# QED_2550_dos_caras.net
KiCad netlist of a schematic drawn in EAGLE
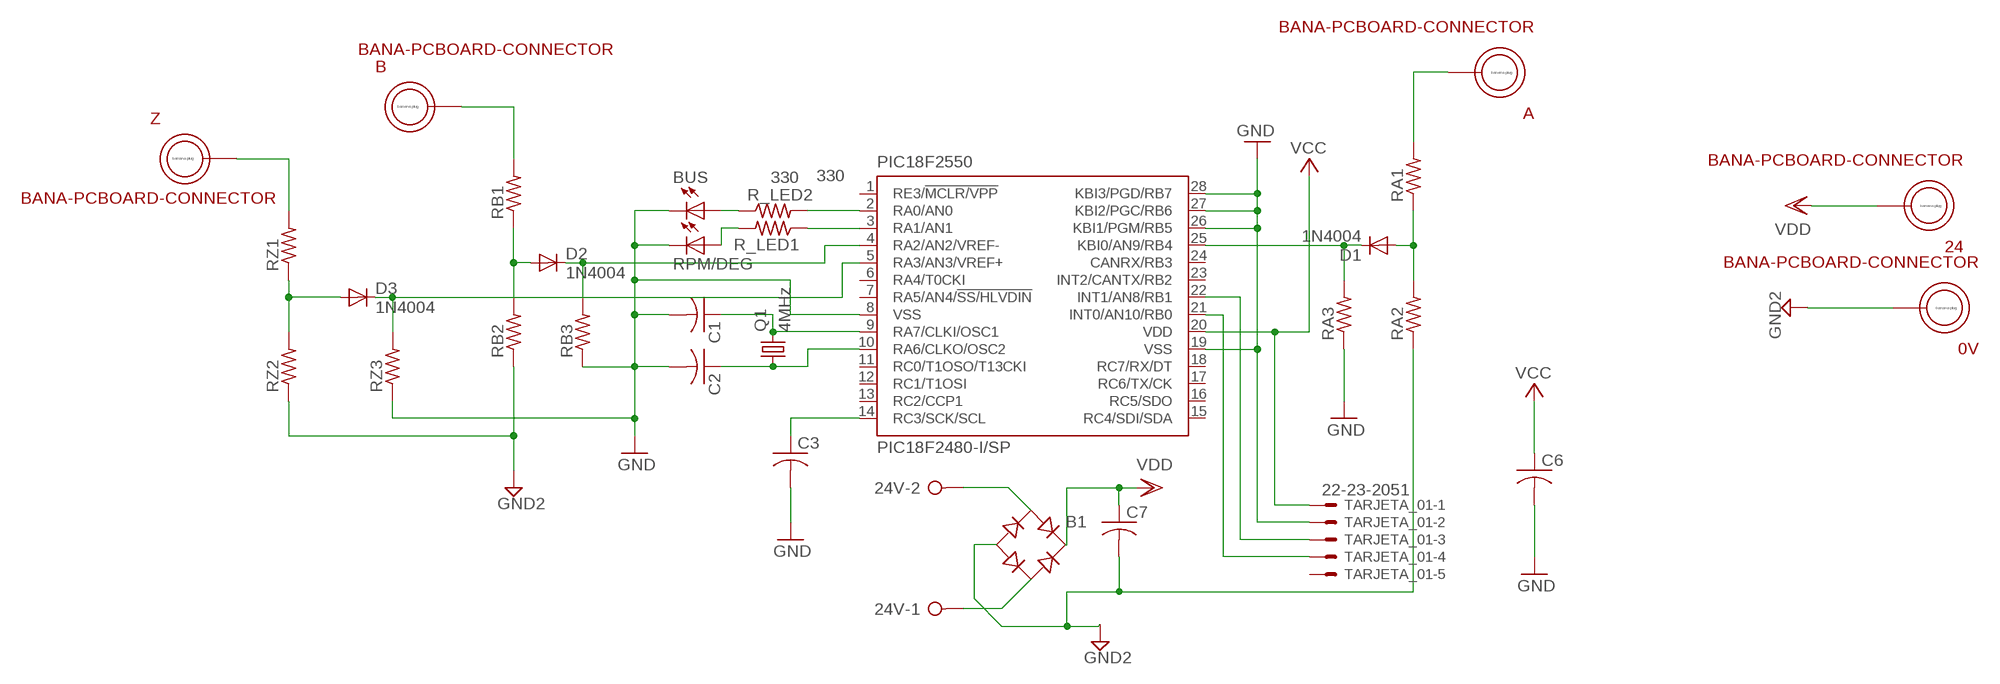
[diagram p0: schematic, sheet 1]

(export (version "E")
  (design (tool "Eeschema 10.0.6"))
  (components
    (comp (ref "0V")
      (value "BANA-PCBOARD-CONNECTOR")
      (footprint "eagle-import:BANA_PLUG")
      (libsource (lib "eagle-import") (part "BANA-PCBOARD-CONNECTOR"))
    )
    (comp (ref "24")
      (value "BANA-PCBOARD-CONNECTOR")
      (footprint "eagle-import:BANA_PLUG")
      (libsource (lib "eagle-import") (part "BANA-PCBOARD-CONNECTOR"))
    )
    (comp (ref "24V")
      (value "W237-02P")
      (footprint "eagle-import:W237-132")
      (libsource (lib "eagle-import") (part "W237-02P"))
    )
    (comp (ref "A")
      (value "BANA-PCBOARD-CONNECTOR")
      (footprint "eagle-import:BANA_PLUG")
      (libsource (lib "eagle-import") (part "BANA-PCBOARD-CONNECTOR"))
    )
    (comp (ref "B")
      (value "BANA-PCBOARD-CONNECTOR")
      (footprint "eagle-import:BANA_PLUG")
      (libsource (lib "eagle-import") (part "BANA-PCBOARD-CONNECTOR"))
    )
    (comp (ref "B1")
      (value "RB1A")
      (footprint "eagle-import:RB1A")
      (libsource (lib "eagle-import") (part "RB1A"))
    )
    (comp (ref "BUS")
      (value "LED5MM")
      (footprint "eagle-import:LED5MM")
      (libsource (lib "eagle-import") (part "LED5MM"))
    )
    (comp (ref "C1")
      (value "C-US025-024X044")
      (footprint "eagle-import:C025-024X044")
      (libsource (lib "eagle-import") (part "C-US025-024X044"))
    )
    (comp (ref "C2")
      (value "C-US025-024X044")
      (footprint "eagle-import:C025-024X044")
      (libsource (lib "eagle-import") (part "C-US025-024X044"))
    )
    (comp (ref "C3")
      (value "C-US025-024X044")
      (footprint "eagle-import:C025-024X044")
      (libsource (lib "eagle-import") (part "C-US025-024X044"))
    )
    (comp (ref "C6")
      (value "C-US025-030X050")
      (footprint "eagle-import:C025-030X050")
      (libsource (lib "eagle-import") (part "C-US025-030X050"))
    )
    (comp (ref "C7")
      (value "C-US025-030X050")
      (footprint "eagle-import:C025-030X050")
      (libsource (lib "eagle-import") (part "C-US025-030X050"))
    )
    (comp (ref "D1")
      (value "1N4004")
      (footprint "eagle-import:DO41-10")
      (libsource (lib "eagle-import") (part "1N4004"))
    )
    (comp (ref "D2")
      (value "1N4004")
      (footprint "eagle-import:DO41-10")
      (libsource (lib "eagle-import") (part "1N4004"))
    )
    (comp (ref "D3")
      (value "1N4004")
      (footprint "eagle-import:DO41-10")
      (libsource (lib "eagle-import") (part "1N4004"))
    )
    (comp (ref "PIC18F2550")
      (value "PIC18F2480-I/SP")
      (footprint "eagle-import:DIL28-3")
      (fields (field (name "MF") "MICROCHIP"))
      (libsource (lib "eagle-import") (part "PIC18F280-I/SP4"))
    )
    (comp (ref "Q1")
      (value "4MHz")
      (footprint "eagle-import:HC49_S")
      (libsource (lib "eagle-import") (part "CRYSTALHC49S"))
    )
    (comp (ref "RA1")
      (value "R-US_0204/7")
      (footprint "eagle-import:0204_7")
      (libsource (lib "eagle-import") (part "R-US_0204/7"))
    )
    (comp (ref "RA2")
      (value "R-US_0204/7")
      (footprint "eagle-import:0204_7")
      (libsource (lib "eagle-import") (part "R-US_0204/7"))
    )
    (comp (ref "RA3")
      (value "R-US_0204/7")
      (footprint "eagle-import:0204_7")
      (libsource (lib "eagle-import") (part "R-US_0204/7"))
    )
    (comp (ref "RB1")
      (value "R-US_0204/7")
      (footprint "eagle-import:0204_7")
      (libsource (lib "eagle-import") (part "R-US_0204/7"))
    )
    (comp (ref "RB2")
      (value "R-US_0204/7")
      (footprint "eagle-import:0204_7")
      (libsource (lib "eagle-import") (part "R-US_0204/7"))
    )
    (comp (ref "RB3")
      (value "R-US_0204/7")
      (footprint "eagle-import:0204_7")
      (libsource (lib "eagle-import") (part "R-US_0204/7"))
    )
    (comp (ref "RPM/DEG")
      (value "LED5MM")
      (footprint "eagle-import:LED5MM")
      (libsource (lib "eagle-import") (part "LED5MM"))
    )
    (comp (ref "RZ1")
      (value "R-US_0204/7")
      (footprint "eagle-import:0204_7")
      (libsource (lib "eagle-import") (part "R-US_0204/7"))
    )
    (comp (ref "RZ2")
      (value "R-US_0204/7")
      (footprint "eagle-import:0204_7")
      (libsource (lib "eagle-import") (part "R-US_0204/7"))
    )
    (comp (ref "RZ3")
      (value "R-US_0204/7")
      (footprint "eagle-import:0204_7")
      (libsource (lib "eagle-import") (part "R-US_0204/7"))
    )
    (comp (ref "R_LED1")
      (value "330")
      (footprint "eagle-import:0204_7")
      (libsource (lib "eagle-import") (part "R-US_0204/7"))
    )
    (comp (ref "R_LED2")
      (value "330")
      (footprint "eagle-import:0204_7")
      (libsource (lib "eagle-import") (part "R-US_0204/7"))
    )
    (comp (ref "TARJETA_01")
      (value "22-23-2051")
      (footprint "eagle-import:22-23-2051")
      (fields (field (name "MF") "MOLEX"))
      (libsource (lib "eagle-import") (part "22-23-2051"))
    )
    (comp (ref "Z")
      (value "BANA-PCBOARD-CONNECTOR")
      (footprint "eagle-import:BANA_PLUG")
      (libsource (lib "eagle-import") (part "BANA-PCBOARD-CONNECTOR"))
    )
  )
  (nets
    (net (code "1") (name "GND") (class "Default")
      (node (ref "BUS") (pin "K") (pinfunction "C_K") (pintype "passive"))
      (node (ref "C1") (pin "2") (pinfunction "2_2") (pintype "passive"))
      (node (ref "C2") (pin "2") (pinfunction "2_2") (pintype "passive"))
      (node (ref "C3") (pin "2") (pinfunction "2_2") (pintype "passive"))
      (node (ref "C6") (pin "2") (pinfunction "2_2") (pintype "passive"))
      (node (ref "PIC18F2550") (pin "19") (pinfunction "VSS_19") (pintype "power_in"))
      (node (ref "PIC18F2550") (pin "26") (pinfunction "KBI1/PGM/RB5_26") (pintype "bidirectional"))
      (node (ref "PIC18F2550") (pin "27") (pinfunction "KBI2/PGC/RB6_27") (pintype "bidirectional"))
      (node (ref "PIC18F2550") (pin "28") (pinfunction "KBI3/PGD/RB7_28") (pintype "bidirectional"))
      (node (ref "PIC18F2550") (pin "8") (pinfunction "VSS_8") (pintype "power_in"))
      (node (ref "RA3") (pin "1") (pinfunction "1_1") (pintype "passive"))
      (node (ref "RB3") (pin "1") (pinfunction "1_1") (pintype "passive"))
      (node (ref "RPM/DEG") (pin "K") (pinfunction "C_K") (pintype "passive"))
      (node (ref "RZ3") (pin "1") (pinfunction "1_1") (pintype "passive"))
      (node (ref "TARJETA_01") (pin "2") (pinfunction "S_2") (pintype "passive"))
    )
    (net (code "2") (name "GND2") (class "Default")
      (node (ref "0V") (pin "P$1") (pinfunction "P$1_P$1") (pintype "bidirectional"))
      (node (ref "B1") (pin "-") (pinfunction "-_-") (pintype "passive"))
      (node (ref "C7") (pin "2") (pinfunction "2_2") (pintype "passive"))
      (node (ref "RA2") (pin "1") (pinfunction "1_1") (pintype "passive"))
      (node (ref "RB2") (pin "1") (pinfunction "1_1") (pintype "passive"))
      (node (ref "RZ2") (pin "1") (pinfunction "1_1") (pintype "passive"))
    )
    (net (code "3") (name "Net-(24VA-KL)") (class "Default")
      (node (ref "24V") (pin "1") (pinfunction "KL_1") (pintype "passive"))
      (node (ref "B1") (pin "AC2") (pinfunction "AC2_AC2") (pintype "passive"))
    )
    (net (code "4") (name "Net-(24VB-KL)") (class "Default")
      (node (ref "24V") (pin "2") (pinfunction "KL_2") (pintype "passive"))
      (node (ref "B1") (pin "AC1") (pinfunction "AC1_AC1") (pintype "passive"))
    )
    (net (code "5") (name "Net-(A-PadP$1)") (class "Default")
      (node (ref "A") (pin "P$1") (pinfunction "P$1_P$1") (pintype "bidirectional"))
      (node (ref "RA1") (pin "2") (pinfunction "2_2") (pintype "passive"))
    )
    (net (code "6") (name "Net-(B-PadP$1)") (class "Default")
      (node (ref "B") (pin "P$1") (pinfunction "P$1_P$1") (pintype "bidirectional"))
      (node (ref "RB1") (pin "2") (pinfunction "2_2") (pintype "passive"))
    )
    (net (code "7") (name "Net-(BUS-PadA)") (class "Default")
      (node (ref "BUS") (pin "A") (pinfunction "A_A") (pintype "passive"))
      (node (ref "R_LED2") (pin "1") (pinfunction "1_1") (pintype "passive"))
    )
    (net (code "8") (name "Net-(D1-PadA)") (class "Default")
      (node (ref "D1") (pin "A") (pinfunction "A_A") (pintype "passive"))
      (node (ref "RA1") (pin "1") (pinfunction "1_1") (pintype "passive"))
      (node (ref "RA2") (pin "2") (pinfunction "2_2") (pintype "passive"))
    )
    (net (code "9") (name "Net-(D2-PadA)") (class "Default")
      (node (ref "D2") (pin "A") (pinfunction "A_A") (pintype "passive"))
      (node (ref "RB1") (pin "1") (pinfunction "1_1") (pintype "passive"))
      (node (ref "RB2") (pin "2") (pinfunction "2_2") (pintype "passive"))
    )
    (net (code "10") (name "Net-(D3-PadA)") (class "Default")
      (node (ref "D3") (pin "A") (pinfunction "A_A") (pintype "passive"))
      (node (ref "RZ1") (pin "1") (pinfunction "1_1") (pintype "passive"))
      (node (ref "RZ2") (pin "2") (pinfunction "2_2") (pintype "passive"))
    )
    (net (code "11") (name "Net-(PIC18F2550-INT0{slash}AN10{slash}RB0)") (class "Default")
      (node (ref "PIC18F2550") (pin "21") (pinfunction "INT0/AN10/RB0_21") (pintype "bidirectional"))
      (node (ref "TARJETA_01") (pin "4") (pinfunction "S_4") (pintype "passive"))
    )
    (net (code "12") (name "Net-(PIC18F2550-INT1{slash}AN8{slash}RB1)") (class "Default")
      (node (ref "PIC18F2550") (pin "22") (pinfunction "INT1/AN8/RB1_22") (pintype "bidirectional"))
      (node (ref "TARJETA_01") (pin "3") (pinfunction "S_3") (pintype "passive"))
    )
    (net (code "13") (name "Net-(PIC18F2550-KBI0{slash}AN9{slash}RB4)") (class "Default")
      (node (ref "D1") (pin "C") (pinfunction "C_C") (pintype "passive"))
      (node (ref "PIC18F2550") (pin "25") (pinfunction "KBI0/AN9/RB4_25") (pintype "bidirectional"))
      (node (ref "RA3") (pin "2") (pinfunction "2_2") (pintype "passive"))
    )
    (net (code "14") (name "Net-(PIC18F2550-RA0{slash}AN0)") (class "Default")
      (node (ref "PIC18F2550") (pin "2") (pinfunction "RA0/AN0_2") (pintype "bidirectional"))
      (node (ref "R_LED2") (pin "2") (pinfunction "2_2") (pintype "passive"))
    )
    (net (code "15") (name "Net-(PIC18F2550-RA1{slash}AN1)") (class "Default")
      (node (ref "PIC18F2550") (pin "3") (pinfunction "RA1/AN1_3") (pintype "bidirectional"))
      (node (ref "R_LED1") (pin "1") (pinfunction "1_1") (pintype "passive"))
    )
    (net (code "16") (name "Net-(PIC18F2550-RA2{slash}AN2{slash}VREF-)") (class "Default")
      (node (ref "D2") (pin "C") (pinfunction "C_C") (pintype "passive"))
      (node (ref "PIC18F2550") (pin "4") (pinfunction "RA2/AN2/VREF-_4") (pintype "bidirectional"))
      (node (ref "RB3") (pin "2") (pinfunction "2_2") (pintype "passive"))
    )
    (net (code "17") (name "Net-(PIC18F2550-RA3{slash}AN3{slash}VREF+)") (class "Default")
      (node (ref "D3") (pin "C") (pinfunction "C_C") (pintype "passive"))
      (node (ref "PIC18F2550") (pin "5") (pinfunction "RA3/AN3/VREF+_5") (pintype "bidirectional"))
      (node (ref "RZ3") (pin "2") (pinfunction "2_2") (pintype "passive"))
    )
    (net (code "18") (name "Net-(PIC18F2550-RA6{slash}CLKO{slash}OSC2)") (class "Default")
      (node (ref "C2") (pin "1") (pinfunction "1_1") (pintype "passive"))
      (node (ref "PIC18F2550") (pin "10") (pinfunction "RA6/CLKO/OSC2_10") (pintype "output"))
      (node (ref "Q1") (pin "1") (pinfunction "1_1") (pintype "passive"))
    )
    (net (code "19") (name "Net-(PIC18F2550-RA7{slash}CLKI{slash}OSC1)") (class "Default")
      (node (ref "C1") (pin "1") (pinfunction "1_1") (pintype "passive"))
      (node (ref "PIC18F2550") (pin "9") (pinfunction "RA7/CLKI/OSC1_9") (pintype "input"))
      (node (ref "Q1") (pin "2") (pinfunction "2_2") (pintype "passive"))
    )
    (net (code "20") (name "Net-(PIC18F2550-RC3{slash}SCK{slash}SCL)") (class "Default")
      (node (ref "C3") (pin "1") (pinfunction "1_1") (pintype "passive"))
      (node (ref "PIC18F2550") (pin "14") (pinfunction "RC3/SCK/SCL_14") (pintype "bidirectional"))
    )
    (net (code "21") (name "Net-(RPM/DEG-PadA)") (class "Default")
      (node (ref "RPM/DEG") (pin "A") (pinfunction "A_A") (pintype "passive"))
      (node (ref "R_LED1") (pin "2") (pinfunction "2_2") (pintype "passive"))
    )
    (net (code "22") (name "Net-(RZ1-Pad2)") (class "Default")
      (node (ref "RZ1") (pin "2") (pinfunction "2_2") (pintype "passive"))
      (node (ref "Z") (pin "P$1") (pinfunction "P$1_P$1") (pintype "bidirectional"))
    )
    (net (code "23") (name "VCC") (class "Default")
      (node (ref "C6") (pin "1") (pinfunction "1_1") (pintype "passive"))
      (node (ref "PIC18F2550") (pin "20") (pinfunction "VDD_20") (pintype "power_in"))
      (node (ref "TARJETA_01") (pin "1") (pinfunction "S_1") (pintype "passive"))
    )
    (net (code "24") (name "VDD") (class "Default")
      (node (ref "24") (pin "P$1") (pinfunction "P$1_P$1") (pintype "bidirectional"))
      (node (ref "B1") (pin "+") (pinfunction "+_+") (pintype "passive"))
      (node (ref "C7") (pin "1") (pinfunction "1_1") (pintype "passive"))
    )
    (net (code "25") (name "unconnected-(PIC18F2550-CANRX{slash}RB3-Pad24)") (class "Default")
      (node (ref "PIC18F2550") (pin "24") (pinfunction "CANRX/RB3_24") (pintype "bidirectional"))
    )
    (net (code "26") (name "unconnected-(PIC18F2550-INT2{slash}CANTX{slash}RB2-Pad23)") (class "Default")
      (node (ref "PIC18F2550") (pin "23") (pinfunction "INT2/CANTX/RB2_23") (pintype "bidirectional"))
    )
    (net (code "27") (name "unconnected-(PIC18F2550-RA4{slash}T0CKI-Pad6)") (class "Default")
      (node (ref "PIC18F2550") (pin "6") (pinfunction "RA4/T0CKI_6") (pintype "bidirectional"))
    )
    (net (code "28") (name "unconnected-(PIC18F2550-RA5{slash}AN4{slash}~{SS{slash}HLVDIN}-Pad7)") (class "Default")
      (node (ref "PIC18F2550") (pin "7") (pinfunction "RA5/AN4/~{SS/HLVDIN}_7") (pintype "bidirectional"))
    )
    (net (code "29") (name "unconnected-(PIC18F2550-RC0{slash}T1OSO{slash}T13CKI-Pad11)") (class "Default")
      (node (ref "PIC18F2550") (pin "11") (pinfunction "RC0/T1OSO/T13CKI_11") (pintype "bidirectional"))
    )
    (net (code "30") (name "unconnected-(PIC18F2550-RC1{slash}T1OSI-Pad12)") (class "Default")
      (node (ref "PIC18F2550") (pin "12") (pinfunction "RC1/T1OSI_12") (pintype "bidirectional"))
    )
    (net (code "31") (name "unconnected-(PIC18F2550-RC2{slash}CCP1-Pad13)") (class "Default")
      (node (ref "PIC18F2550") (pin "13") (pinfunction "RC2/CCP1_13") (pintype "bidirectional"))
    )
    (net (code "32") (name "unconnected-(PIC18F2550-RC4{slash}SDI{slash}SDA-Pad15)") (class "Default")
      (node (ref "PIC18F2550") (pin "15") (pinfunction "RC4/SDI/SDA_15") (pintype "bidirectional"))
    )
    (net (code "33") (name "unconnected-(PIC18F2550-RC5{slash}SDO-Pad16)") (class "Default")
      (node (ref "PIC18F2550") (pin "16") (pinfunction "RC5/SDO_16") (pintype "bidirectional"))
    )
    (net (code "34") (name "unconnected-(PIC18F2550-RC6{slash}TX{slash}CK-Pad17)") (class "Default")
      (node (ref "PIC18F2550") (pin "17") (pinfunction "RC6/TX/CK_17") (pintype "bidirectional"))
    )
    (net (code "35") (name "unconnected-(PIC18F2550-RC7{slash}RX{slash}DT-Pad18)") (class "Default")
      (node (ref "PIC18F2550") (pin "18") (pinfunction "RC7/RX/DT_18") (pintype "bidirectional"))
    )
    (net (code "36") (name "unconnected-(PIC18F2550-RE3{slash}~{MCLR{slash}VPP}-Pad1)") (class "Default")
      (node (ref "PIC18F2550") (pin "1") (pinfunction "RE3/~{MCLR/VPP}_1") (pintype "input"))
    )
    (net (code "37") (name "unconnected-(TARJETA_01E-S-Pad5)") (class "Default")
      (node (ref "TARJETA_01") (pin "5") (pinfunction "S_5") (pintype "passive"))
    )
  )
)
